# pt1MX.net
KiCad netlist of a schematic drawn in EAGLE
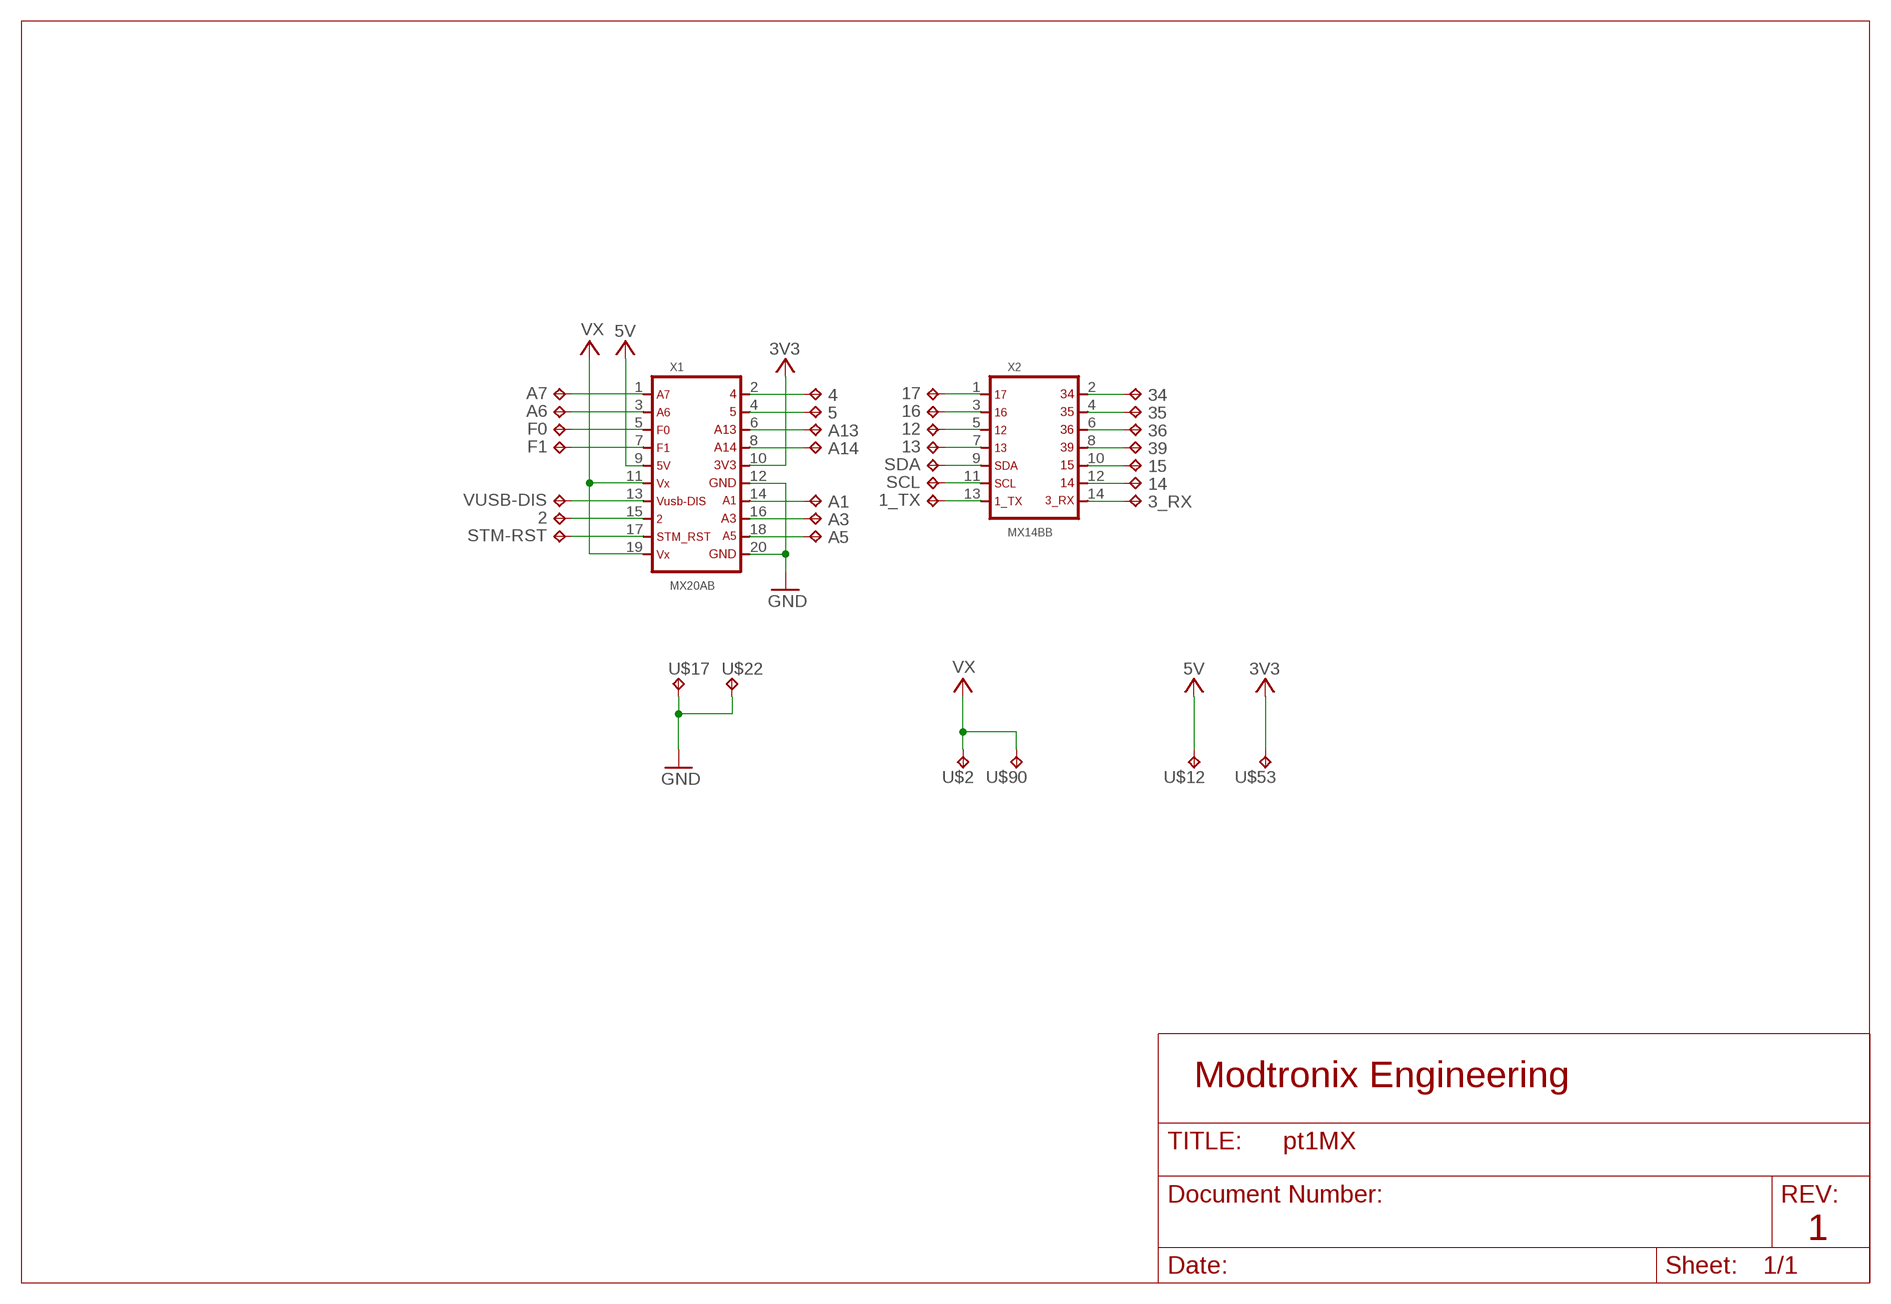
[diagram p0: schematic, sheet 1]

(export (version "E")
  (design (tool "Eeschema 10.0.6"))
  (components
    (comp (ref "1_TX")
      (value "TPD10-D200")
      (footprint "eagle-import:TP-10-D200")
      (libsource (lib "eagle-import") (part "TPD10-D200"))
    )
    (comp (ref "2")
      (value "TPD10-D200")
      (footprint "eagle-import:TP-10-D200")
      (libsource (lib "eagle-import") (part "TPD10-D200"))
    )
    (comp (ref "3_RX")
      (value "TPD10-D200")
      (footprint "eagle-import:TP-10-D200")
      (libsource (lib "eagle-import") (part "TPD10-D200"))
    )
    (comp (ref "4")
      (value "TPD10-D200")
      (footprint "eagle-import:TP-10-D200")
      (libsource (lib "eagle-import") (part "TPD10-D200"))
    )
    (comp (ref "5")
      (value "TPD10-D200")
      (footprint "eagle-import:TP-10-D200")
      (libsource (lib "eagle-import") (part "TPD10-D200"))
    )
    (comp (ref "12")
      (value "TPD10-D200")
      (footprint "eagle-import:TP-10-D200")
      (libsource (lib "eagle-import") (part "TPD10-D200"))
    )
    (comp (ref "13")
      (value "TPD10-D200")
      (footprint "eagle-import:TP-10-D200")
      (libsource (lib "eagle-import") (part "TPD10-D200"))
    )
    (comp (ref "14")
      (value "TPD10-D200")
      (footprint "eagle-import:TP-10-D200")
      (libsource (lib "eagle-import") (part "TPD10-D200"))
    )
    (comp (ref "15")
      (value "TPD10-D200")
      (footprint "eagle-import:TP-10-D200")
      (libsource (lib "eagle-import") (part "TPD10-D200"))
    )
    (comp (ref "16")
      (value "TPD10-D200")
      (footprint "eagle-import:TP-10-D200")
      (libsource (lib "eagle-import") (part "TPD10-D200"))
    )
    (comp (ref "17")
      (value "TPD10-D200")
      (footprint "eagle-import:TP-10-D200")
      (libsource (lib "eagle-import") (part "TPD10-D200"))
    )
    (comp (ref "34")
      (value "TPD10-D200")
      (footprint "eagle-import:TP-10-D200")
      (libsource (lib "eagle-import") (part "TPD10-D200"))
    )
    (comp (ref "35")
      (value "TPD10-D200")
      (footprint "eagle-import:TP-10-D200")
      (libsource (lib "eagle-import") (part "TPD10-D200"))
    )
    (comp (ref "36")
      (value "TPD10-D200")
      (footprint "eagle-import:TP-10-D200")
      (libsource (lib "eagle-import") (part "TPD10-D200"))
    )
    (comp (ref "39")
      (value "TPD10-D200")
      (footprint "eagle-import:TP-10-D200")
      (libsource (lib "eagle-import") (part "TPD10-D200"))
    )
    (comp (ref "A1")
      (value "TPD10-D200")
      (footprint "eagle-import:TP-10-D200")
      (libsource (lib "eagle-import") (part "TPD10-D200"))
    )
    (comp (ref "A3")
      (value "TPD10-D200")
      (footprint "eagle-import:TP-10-D200")
      (libsource (lib "eagle-import") (part "TPD10-D200"))
    )
    (comp (ref "A5")
      (value "TPD10-D200")
      (footprint "eagle-import:TP-10-D200")
      (libsource (lib "eagle-import") (part "TPD10-D200"))
    )
    (comp (ref "A6")
      (value "TPD10-D200")
      (footprint "eagle-import:TP-10-D200")
      (libsource (lib "eagle-import") (part "TPD10-D200"))
    )
    (comp (ref "A7")
      (value "TPD10-D200")
      (footprint "eagle-import:TP-10-D200")
      (libsource (lib "eagle-import") (part "TPD10-D200"))
    )
    (comp (ref "A13")
      (value "TPD10-D200")
      (footprint "eagle-import:TP-10-D200")
      (libsource (lib "eagle-import") (part "TPD10-D200"))
    )
    (comp (ref "A14")
      (value "TPD10-D200")
      (footprint "eagle-import:TP-10-D200")
      (libsource (lib "eagle-import") (part "TPD10-D200"))
    )
    (comp (ref "F0")
      (value "TPD10-D200")
      (footprint "eagle-import:TP-10-D200")
      (libsource (lib "eagle-import") (part "TPD10-D200"))
    )
    (comp (ref "F1")
      (value "TPD10-D200")
      (footprint "eagle-import:TP-10-D200")
      (libsource (lib "eagle-import") (part "TPD10-D200"))
    )
    (comp (ref "SCL")
      (value "TPD10-D200")
      (footprint "eagle-import:TP-10-D200")
      (libsource (lib "eagle-import") (part "TPD10-D200"))
    )
    (comp (ref "SDA")
      (value "TPD10-D200")
      (footprint "eagle-import:TP-10-D200")
      (libsource (lib "eagle-import") (part "TPD10-D200"))
    )
    (comp (ref "STM-RST")
      (value "TPD10-D200")
      (footprint "eagle-import:TP-10-D200")
      (libsource (lib "eagle-import") (part "TPD10-D200"))
    )
    (comp (ref "U$2")
      (value "TPD10-D200")
      (footprint "eagle-import:TP-10-D200")
      (libsource (lib "eagle-import") (part "TPD10-D200"))
    )
    (comp (ref "U$12")
      (value "TPD10-D200")
      (footprint "eagle-import:TP-10-D200")
      (libsource (lib "eagle-import") (part "TPD10-D200"))
    )
    (comp (ref "U$17")
      (value "TPD10-D200")
      (footprint "eagle-import:TP-10-D200")
      (libsource (lib "eagle-import") (part "TPD10-D200"))
    )
    (comp (ref "U$22")
      (value "TPD10-D200")
      (footprint "eagle-import:TP-10-D200")
      (libsource (lib "eagle-import") (part "TPD10-D200"))
    )
    (comp (ref "U$53")
      (value "TPD10-D200")
      (footprint "eagle-import:TP-10-D200")
      (libsource (lib "eagle-import") (part "TPD10-D200"))
    )
    (comp (ref "U$90")
      (value "TPD10-D200")
      (footprint "eagle-import:TP-10-D200")
      (libsource (lib "eagle-import") (part "TPD10-D200"))
    )
    (comp (ref "VUSB-DIS")
      (value "TPD10-D200")
      (footprint "eagle-import:TP-10-D200")
      (libsource (lib "eagle-import") (part "TPD10-D200"))
    )
    (comp (ref "X1")
      (value "MX20AB")
      (footprint "eagle-import:MA10-2-NONUM")
      (libsource (lib "eagle-import") (part "MX20AB"))
    )
    (comp (ref "X2")
      (value "MX14BB")
      (footprint "eagle-import:MA07-2-NONUM")
      (libsource (lib "eagle-import") (part "MX14BB"))
    )
  )
  (nets
    (net (code "1") (name "3V3") (class "Default")
      (node (ref "U$53") (pin "1") (pinfunction "TP_1") (pintype "input"))
      (node (ref "X1") (pin "10") (pinfunction "10_10") (pintype "passive"))
    )
    (net (code "2") (name "5V") (class "Default")
      (node (ref "U$12") (pin "1") (pinfunction "TP_1") (pintype "input"))
      (node (ref "X1") (pin "9") (pinfunction "9_9") (pintype "passive"))
    )
    (net (code "3") (name "GND") (class "Default")
      (node (ref "U$17") (pin "1") (pinfunction "TP_1") (pintype "input"))
      (node (ref "U$22") (pin "1") (pinfunction "TP_1") (pintype "input"))
      (node (ref "X1") (pin "12") (pinfunction "12_12") (pintype "passive"))
      (node (ref "X1") (pin "20") (pinfunction "20_20") (pintype "passive"))
    )
    (net (code "4") (name "Net-(1_TX-TP)") (class "Default")
      (node (ref "1_TX") (pin "1") (pinfunction "TP_1") (pintype "input"))
      (node (ref "X2") (pin "13") (pinfunction "13_13") (pintype "passive"))
    )
    (net (code "5") (name "Net-(2-TP)") (class "Default")
      (node (ref "2") (pin "1") (pinfunction "TP_1") (pintype "input"))
      (node (ref "X1") (pin "15") (pinfunction "15_15") (pintype "passive"))
    )
    (net (code "6") (name "Net-(3_RX-TP)") (class "Default")
      (node (ref "3_RX") (pin "1") (pinfunction "TP_1") (pintype "input"))
      (node (ref "X2") (pin "14") (pinfunction "14_14") (pintype "passive"))
    )
    (net (code "7") (name "Net-(4-TP)") (class "Default")
      (node (ref "4") (pin "1") (pinfunction "TP_1") (pintype "input"))
      (node (ref "X1") (pin "2") (pinfunction "2_2") (pintype "passive"))
    )
    (net (code "8") (name "Net-(5-TP)") (class "Default")
      (node (ref "5") (pin "1") (pinfunction "TP_1") (pintype "input"))
      (node (ref "X1") (pin "4") (pinfunction "4_4") (pintype "passive"))
    )
    (net (code "9") (name "Net-(12-TP)") (class "Default")
      (node (ref "12") (pin "1") (pinfunction "TP_1") (pintype "input"))
      (node (ref "X2") (pin "5") (pinfunction "5_5") (pintype "passive"))
    )
    (net (code "10") (name "Net-(13-TP)") (class "Default")
      (node (ref "13") (pin "1") (pinfunction "TP_1") (pintype "input"))
      (node (ref "X2") (pin "7") (pinfunction "7_7") (pintype "passive"))
    )
    (net (code "11") (name "Net-(14-TP)") (class "Default")
      (node (ref "14") (pin "1") (pinfunction "TP_1") (pintype "input"))
      (node (ref "X2") (pin "12") (pinfunction "12_12") (pintype "passive"))
    )
    (net (code "12") (name "Net-(15-TP)") (class "Default")
      (node (ref "15") (pin "1") (pinfunction "TP_1") (pintype "input"))
      (node (ref "X2") (pin "10") (pinfunction "10_10") (pintype "passive"))
    )
    (net (code "13") (name "Net-(16-TP)") (class "Default")
      (node (ref "16") (pin "1") (pinfunction "TP_1") (pintype "input"))
      (node (ref "X2") (pin "3") (pinfunction "3_3") (pintype "passive"))
    )
    (net (code "14") (name "Net-(17-TP)") (class "Default")
      (node (ref "17") (pin "1") (pinfunction "TP_1") (pintype "input"))
      (node (ref "X2") (pin "1") (pinfunction "1_1") (pintype "passive"))
    )
    (net (code "15") (name "Net-(34-TP)") (class "Default")
      (node (ref "34") (pin "1") (pinfunction "TP_1") (pintype "input"))
      (node (ref "X2") (pin "2") (pinfunction "2_2") (pintype "passive"))
    )
    (net (code "16") (name "Net-(35-TP)") (class "Default")
      (node (ref "35") (pin "1") (pinfunction "TP_1") (pintype "input"))
      (node (ref "X2") (pin "4") (pinfunction "4_4") (pintype "passive"))
    )
    (net (code "17") (name "Net-(36-TP)") (class "Default")
      (node (ref "36") (pin "1") (pinfunction "TP_1") (pintype "input"))
      (node (ref "X2") (pin "6") (pinfunction "6_6") (pintype "passive"))
    )
    (net (code "18") (name "Net-(39-TP)") (class "Default")
      (node (ref "39") (pin "1") (pinfunction "TP_1") (pintype "input"))
      (node (ref "X2") (pin "8") (pinfunction "8_8") (pintype "passive"))
    )
    (net (code "19") (name "Net-(A1-TP)") (class "Default")
      (node (ref "A1") (pin "1") (pinfunction "TP_1") (pintype "input"))
      (node (ref "X1") (pin "14") (pinfunction "14_14") (pintype "passive"))
    )
    (net (code "20") (name "Net-(A3-TP)") (class "Default")
      (node (ref "A3") (pin "1") (pinfunction "TP_1") (pintype "input"))
      (node (ref "X1") (pin "16") (pinfunction "16_16") (pintype "passive"))
    )
    (net (code "21") (name "Net-(A5-TP)") (class "Default")
      (node (ref "A5") (pin "1") (pinfunction "TP_1") (pintype "input"))
      (node (ref "X1") (pin "18") (pinfunction "18_18") (pintype "passive"))
    )
    (net (code "22") (name "Net-(A6-TP)") (class "Default")
      (node (ref "A6") (pin "1") (pinfunction "TP_1") (pintype "input"))
      (node (ref "X1") (pin "3") (pinfunction "3_3") (pintype "passive"))
    )
    (net (code "23") (name "Net-(A7-TP)") (class "Default")
      (node (ref "A7") (pin "1") (pinfunction "TP_1") (pintype "input"))
      (node (ref "X1") (pin "1") (pinfunction "1_1") (pintype "passive"))
    )
    (net (code "24") (name "Net-(A13-TP)") (class "Default")
      (node (ref "A13") (pin "1") (pinfunction "TP_1") (pintype "input"))
      (node (ref "X1") (pin "6") (pinfunction "6_6") (pintype "passive"))
    )
    (net (code "25") (name "Net-(A14-TP)") (class "Default")
      (node (ref "A14") (pin "1") (pinfunction "TP_1") (pintype "input"))
      (node (ref "X1") (pin "8") (pinfunction "8_8") (pintype "passive"))
    )
    (net (code "26") (name "Net-(F0-TP)") (class "Default")
      (node (ref "F0") (pin "1") (pinfunction "TP_1") (pintype "input"))
      (node (ref "X1") (pin "5") (pinfunction "5_5") (pintype "passive"))
    )
    (net (code "27") (name "Net-(F1-TP)") (class "Default")
      (node (ref "F1") (pin "1") (pinfunction "TP_1") (pintype "input"))
      (node (ref "X1") (pin "7") (pinfunction "7_7") (pintype "passive"))
    )
    (net (code "28") (name "Net-(SCL-TP)") (class "Default")
      (node (ref "SCL") (pin "1") (pinfunction "TP_1") (pintype "input"))
      (node (ref "X2") (pin "11") (pinfunction "11_11") (pintype "passive"))
    )
    (net (code "29") (name "Net-(SDA-TP)") (class "Default")
      (node (ref "SDA") (pin "1") (pinfunction "TP_1") (pintype "input"))
      (node (ref "X2") (pin "9") (pinfunction "9_9") (pintype "passive"))
    )
    (net (code "30") (name "Net-(STM-RST-TP)") (class "Default")
      (node (ref "STM-RST") (pin "1") (pinfunction "TP_1") (pintype "input"))
      (node (ref "X1") (pin "17") (pinfunction "17_17") (pintype "passive"))
    )
    (net (code "31") (name "Net-(VUSB-DIS-TP)") (class "Default")
      (node (ref "VUSB-DIS") (pin "1") (pinfunction "TP_1") (pintype "input"))
      (node (ref "X1") (pin "13") (pinfunction "13_13") (pintype "passive"))
    )
    (net (code "32") (name "VX") (class "Default")
      (node (ref "U$2") (pin "1") (pinfunction "TP_1") (pintype "input"))
      (node (ref "U$90") (pin "1") (pinfunction "TP_1") (pintype "input"))
      (node (ref "X1") (pin "11") (pinfunction "11_11") (pintype "passive"))
      (node (ref "X1") (pin "19") (pinfunction "19_19") (pintype "passive"))
    )
  )
)
